# taGPS-1350.net
KiCad netlist of a schematic drawn in EAGLE
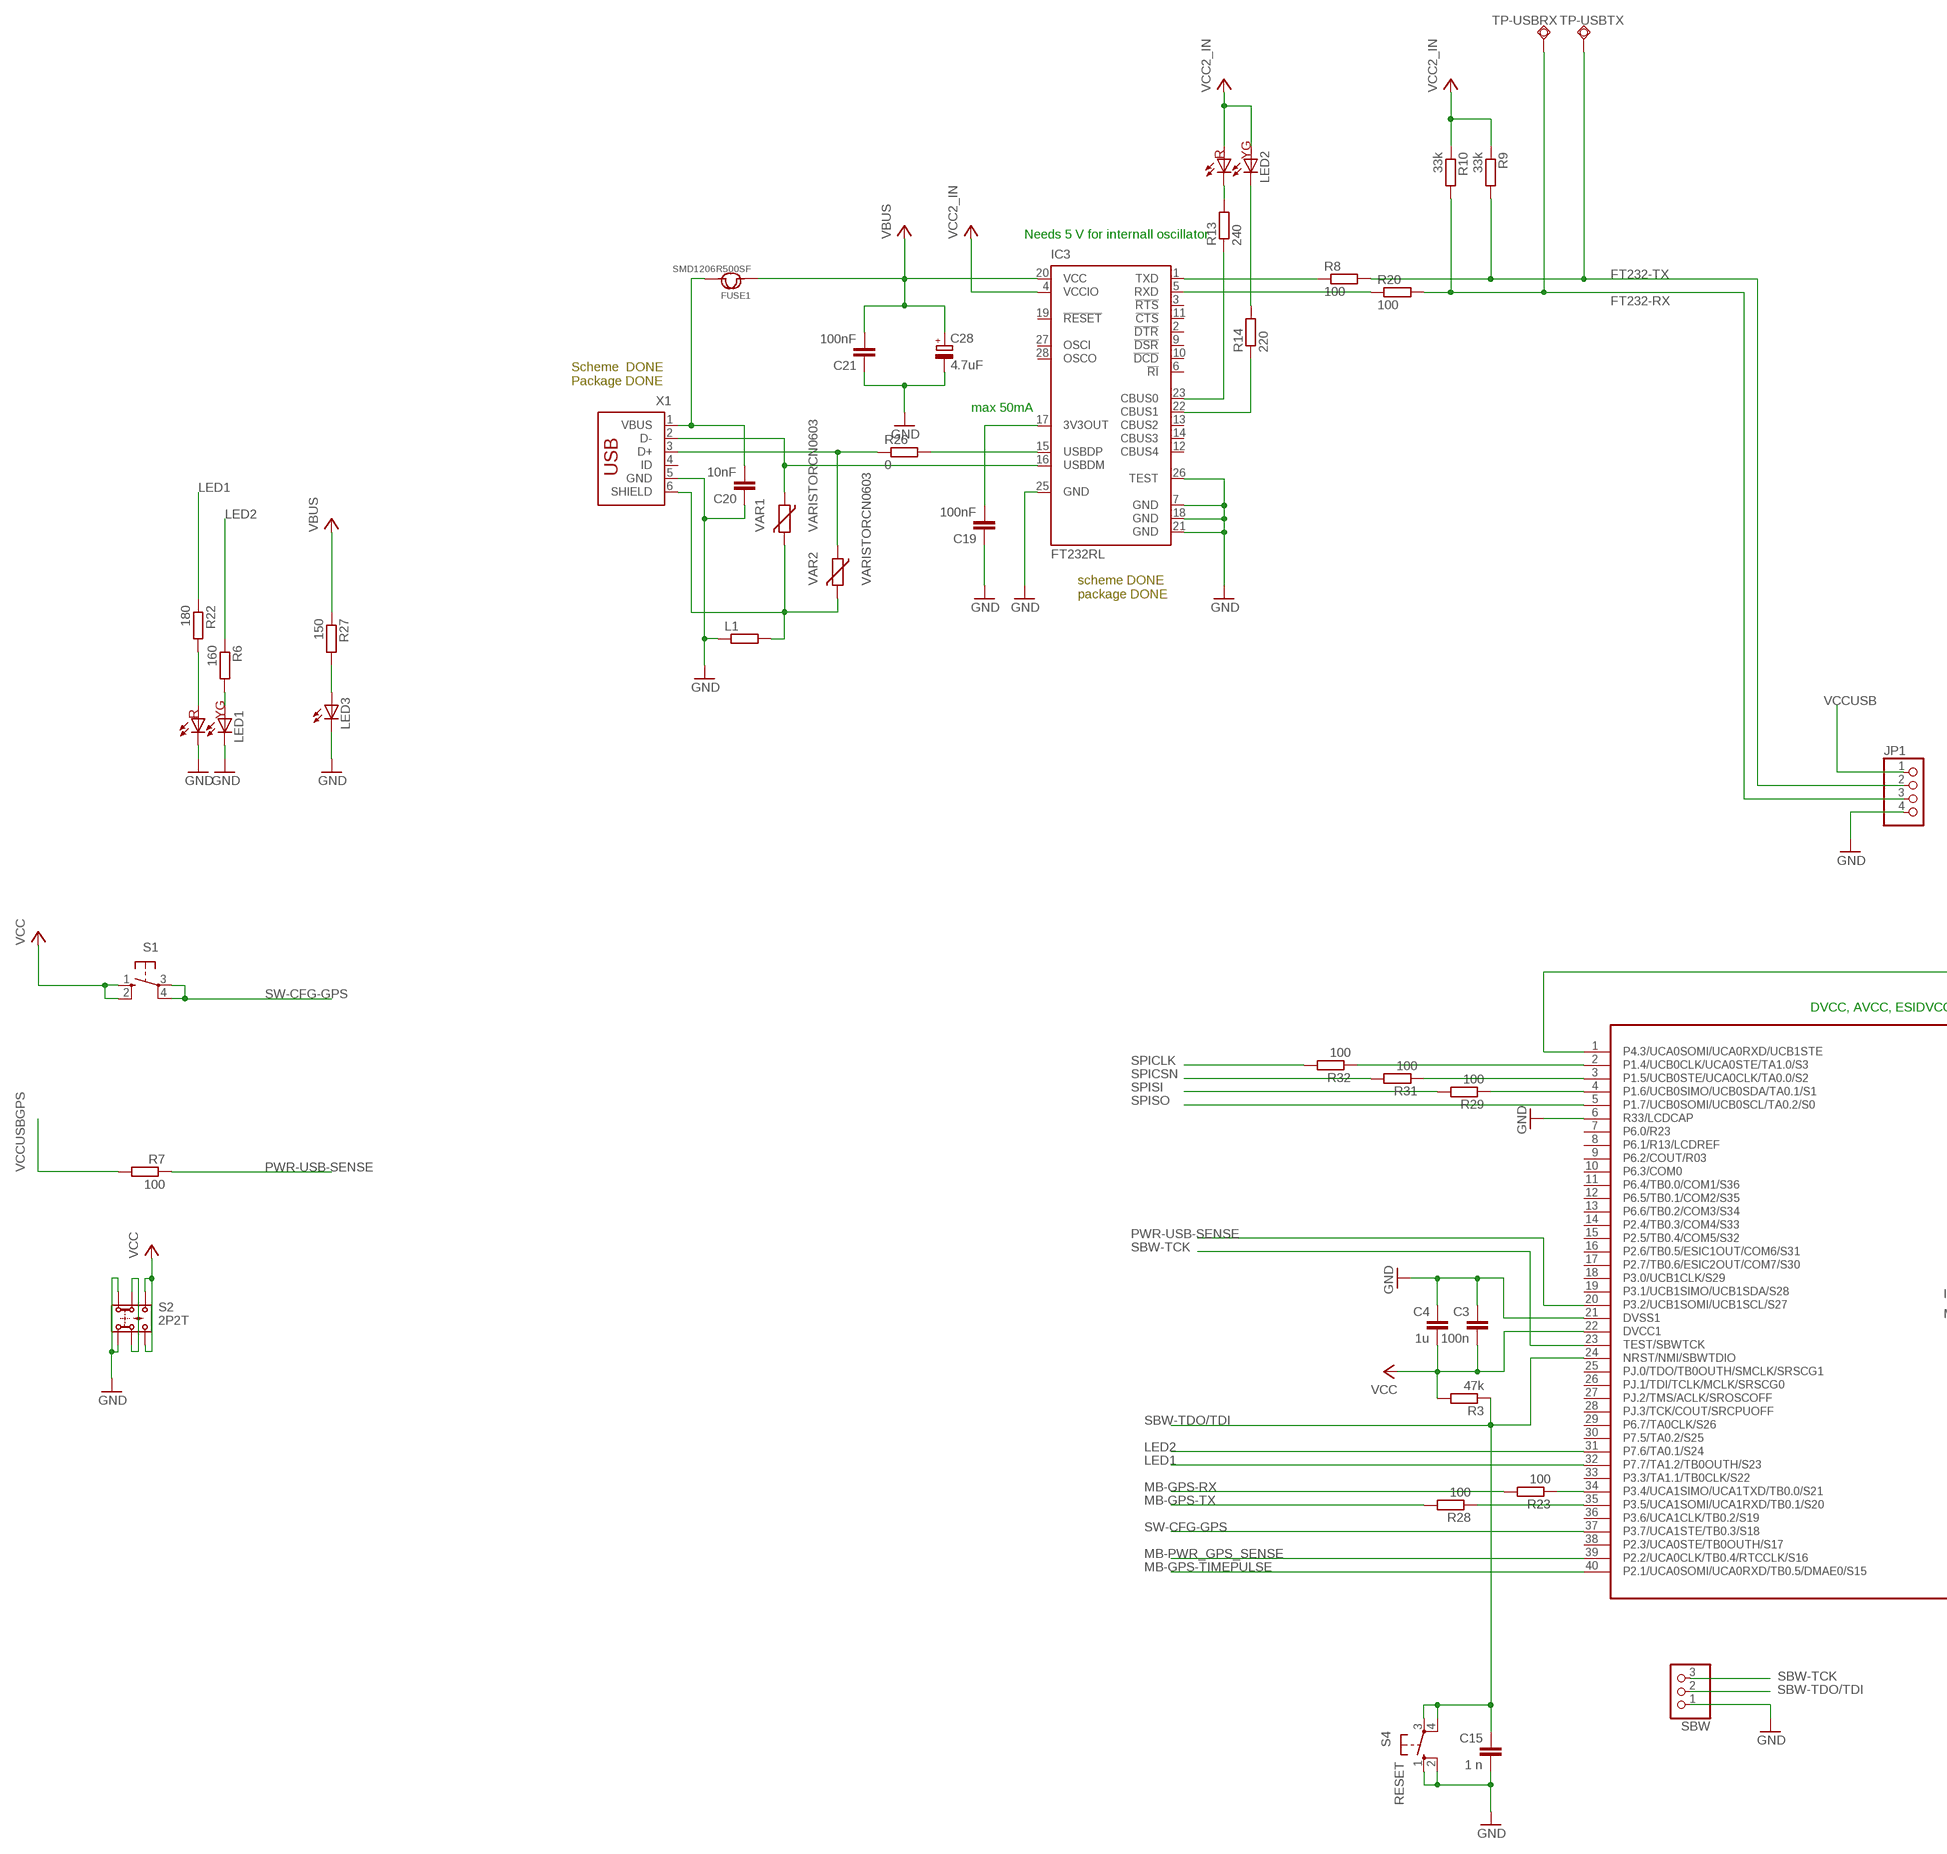
[diagram p0: schematic, sheet 1, part 1 of 2]
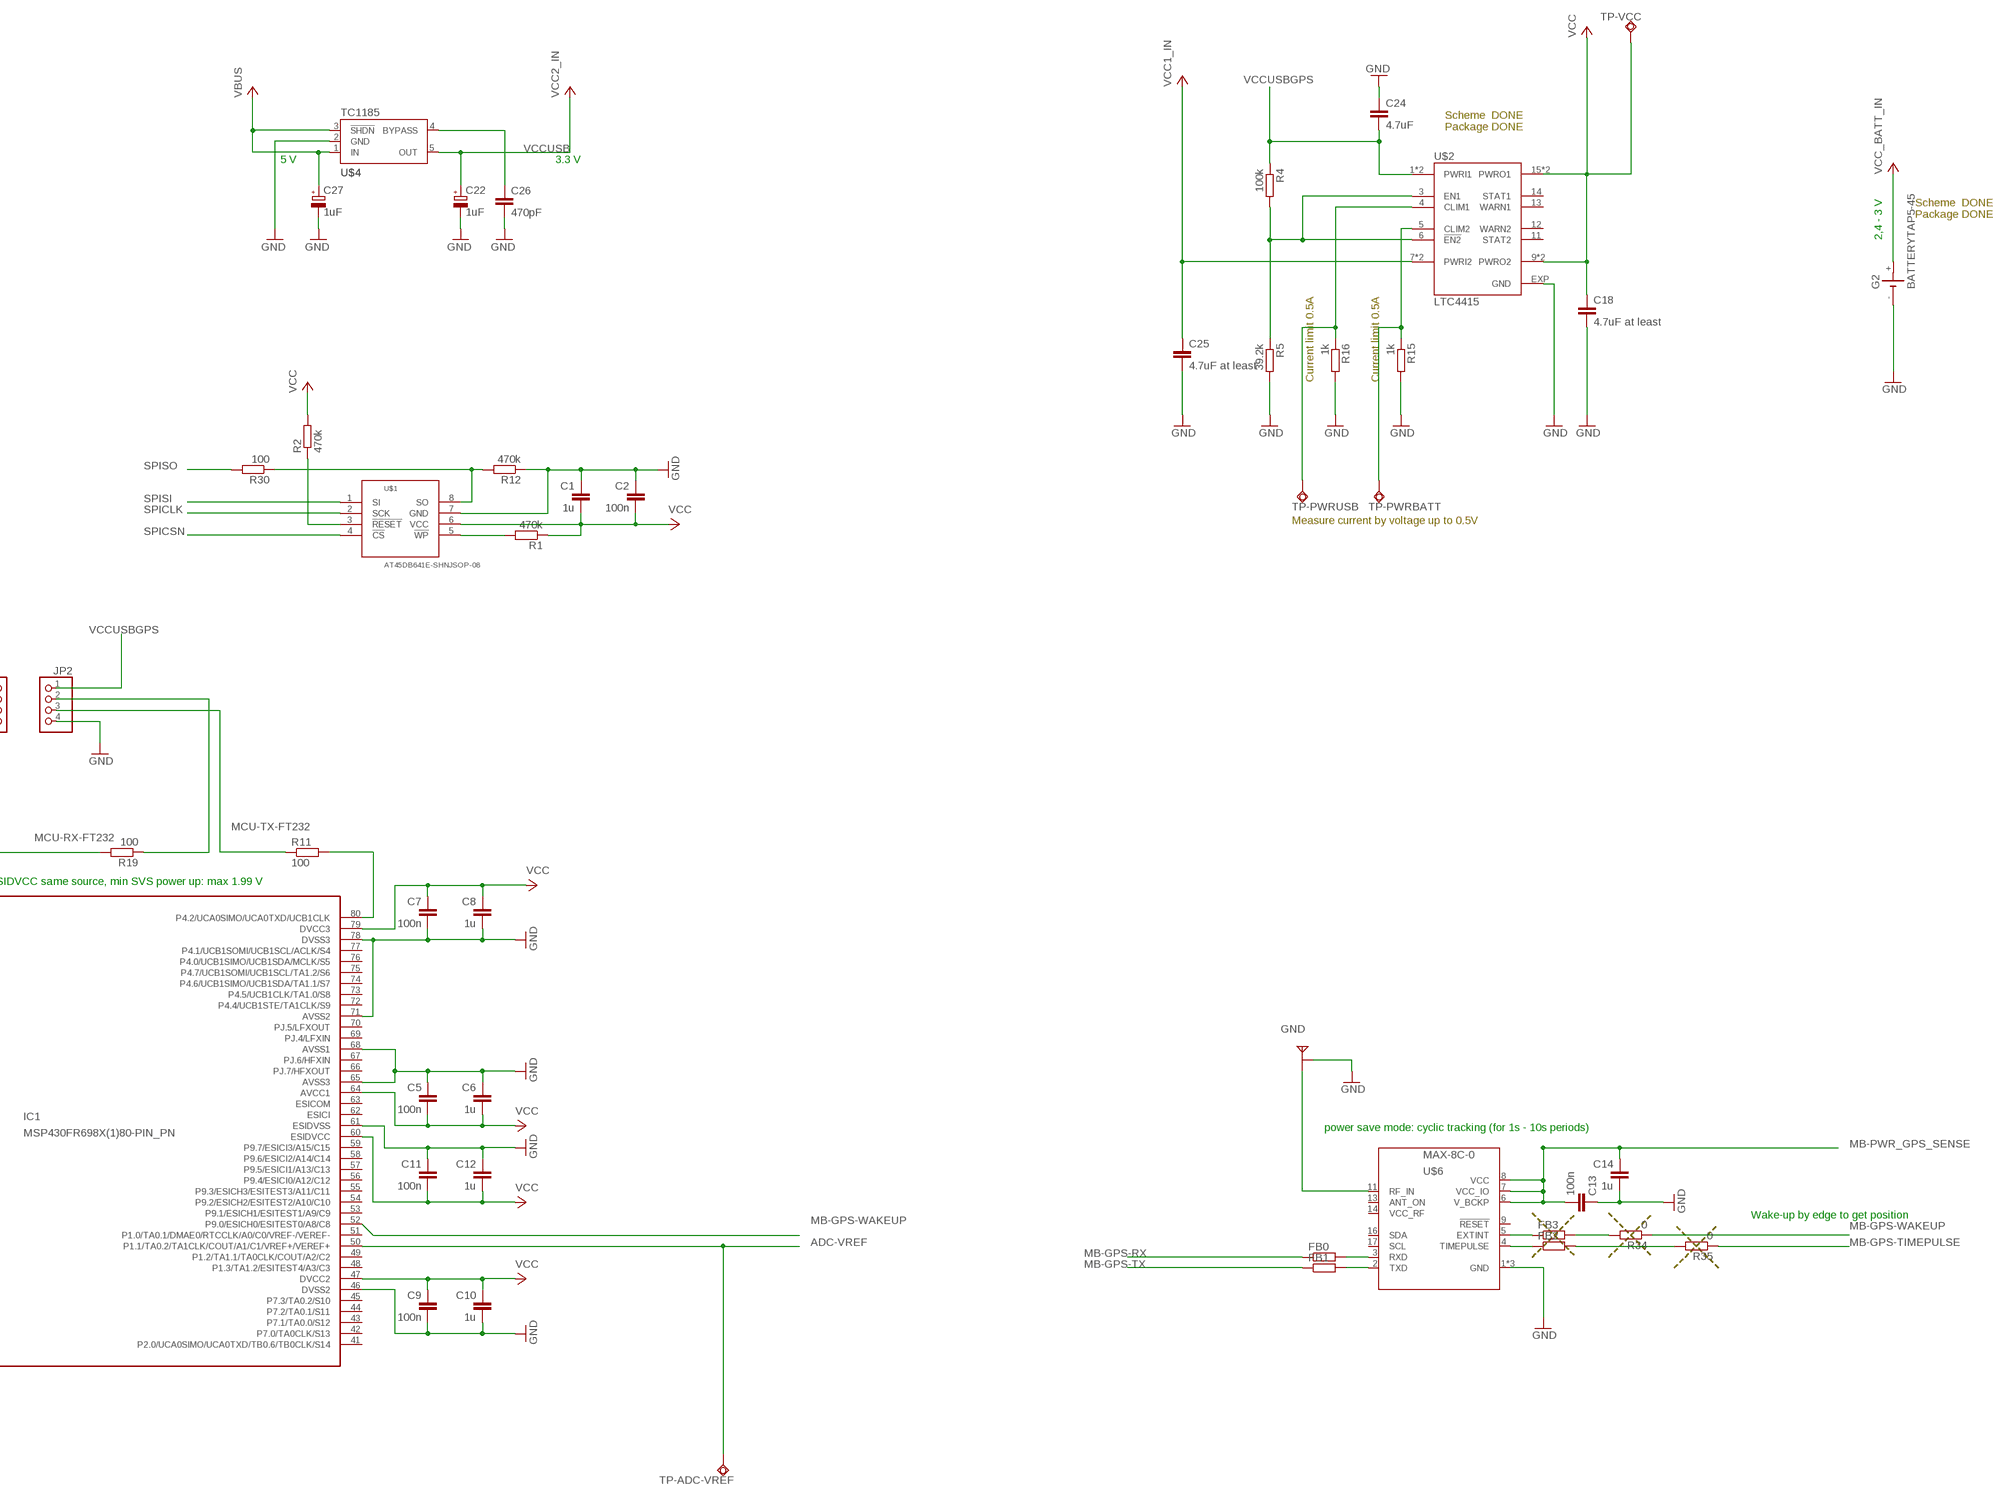
[diagram p1: schematic, sheet 1, part 2 of 2]

(export (version "E")
  (design (tool "Eeschema 10.0.6"))
  (components
    (comp (ref "C1")
      (value "1u")
      (footprint "eagle-import:C0603")
      (libsource (lib "eagle-import") (part "C-EUC0603"))
    )
    (comp (ref "C2")
      (value "100n")
      (footprint "eagle-import:C0603")
      (libsource (lib "eagle-import") (part "C-EUC0603"))
    )
    (comp (ref "C3")
      (value "100n")
      (footprint "eagle-import:C0603")
      (libsource (lib "eagle-import") (part "C-EUC0603"))
    )
    (comp (ref "C4")
      (value "1u")
      (footprint "eagle-import:C0603")
      (libsource (lib "eagle-import") (part "C-EUC0603"))
    )
    (comp (ref "C5")
      (value "100n")
      (footprint "eagle-import:C0603")
      (libsource (lib "eagle-import") (part "C-EUC0603"))
    )
    (comp (ref "C6")
      (value "1u")
      (footprint "eagle-import:C0603")
      (libsource (lib "eagle-import") (part "C-EUC0603"))
    )
    (comp (ref "C7")
      (value "100n")
      (footprint "eagle-import:C0603")
      (libsource (lib "eagle-import") (part "C-EUC0603"))
    )
    (comp (ref "C8")
      (value "1u")
      (footprint "eagle-import:C0603")
      (libsource (lib "eagle-import") (part "C-EUC0603"))
    )
    (comp (ref "C9")
      (value "100n")
      (footprint "eagle-import:C0603")
      (libsource (lib "eagle-import") (part "C-EUC0603"))
    )
    (comp (ref "C10")
      (value "1u")
      (footprint "eagle-import:C0603")
      (libsource (lib "eagle-import") (part "C-EUC0603"))
    )
    (comp (ref "C11")
      (value "100n")
      (footprint "eagle-import:C0603")
      (libsource (lib "eagle-import") (part "C-EUC0603"))
    )
    (comp (ref "C12")
      (value "1u")
      (footprint "eagle-import:C0603")
      (libsource (lib "eagle-import") (part "C-EUC0603"))
    )
    (comp (ref "C13")
      (value "100n")
      (footprint "eagle-import:C0603")
      (libsource (lib "eagle-import") (part "C-EUC0603"))
    )
    (comp (ref "C14")
      (value "1u")
      (footprint "eagle-import:C0603")
      (libsource (lib "eagle-import") (part "C-EUC0603"))
    )
    (comp (ref "C15")
      (value "1 n")
      (footprint "eagle-import:C0603")
      (libsource (lib "eagle-import") (part "C-EUC0603"))
    )
    (comp (ref "C18")
      (value "4.7uF at least")
      (footprint "eagle-import:C0805")
      (libsource (lib "eagle-import") (part "C-EUC0805"))
    )
    (comp (ref "C19")
      (value "100nF")
      (footprint "eagle-import:C0603")
      (libsource (lib "eagle-import") (part "C-EUC0603"))
    )
    (comp (ref "C20")
      (value "10nF")
      (footprint "eagle-import:C0603")
      (libsource (lib "eagle-import") (part "C-EUC0603"))
    )
    (comp (ref "C21")
      (value "100nF")
      (footprint "eagle-import:C0603")
      (libsource (lib "eagle-import") (part "C-EUC0603"))
    )
    (comp (ref "C22")
      (value "1uF")
      (footprint "eagle-import:A_3216-18W")
      (libsource (lib "eagle-import") (part "CPOL-EUA/3216-18W"))
    )
    (comp (ref "C24")
      (value "4.7uF")
      (footprint "eagle-import:C0805")
      (libsource (lib "eagle-import") (part "C-EUC0805"))
    )
    (comp (ref "C25")
      (value "4.7uF at least")
      (footprint "eagle-import:C0805")
      (libsource (lib "eagle-import") (part "C-EUC0805"))
    )
    (comp (ref "C26")
      (value "470pF")
      (footprint "eagle-import:C0603")
      (libsource (lib "eagle-import") (part "C-EUC0603"))
    )
    (comp (ref "C27")
      (value "1uF")
      (footprint "eagle-import:A_3216-18W")
      (libsource (lib "eagle-import") (part "CPOL-EUA/3216-18W"))
    )
    (comp (ref "C28")
      (value "4.7uF")
      (footprint "eagle-import:A_3216-18W")
      (libsource (lib "eagle-import") (part "CPOL-EUA/3216-18W"))
    )
    (comp (ref "FB0")
      (value "R-EU_R0402")
      (footprint "eagle-import:R0402")
      (libsource (lib "eagle-import") (part "R-EU_R0402"))
    )
    (comp (ref "FB1")
      (value "R-EU_R0402")
      (footprint "eagle-import:R0402")
      (libsource (lib "eagle-import") (part "R-EU_R0402"))
    )
    (comp (ref "FB2")
      (value "R-EU_R0402")
      (footprint "eagle-import:R0402")
      (libsource (lib "eagle-import") (part "R-EU_R0402"))
    )
    (comp (ref "FB3")
      (value "R-EU_R0402")
      (footprint "eagle-import:R0402")
      (libsource (lib "eagle-import") (part "R-EU_R0402"))
    )
    (comp (ref "FUSE1")
      (value "SMD1206R500SF")
      (footprint "eagle-import:F1812")
      (libsource (lib "eagle-import") (part "SMD-PPTC-500MA-15V(1812)"))
    )
    (comp (ref "G2")
      (value "BATTERYTAP5-45")
      (footprint "eagle-import:TAP5-45")
      (libsource (lib "eagle-import") (part "BATTERYTAP5-45"))
    )
    (comp (ref "IC1")
      (value "MSP430FR698X(1)80-PIN_PN")
      (footprint "eagle-import:PN_S-PQFP-G80")
      (libsource (lib "eagle-import") (part "MSP430FR698X(1)80-PIN_PN"))
    )
    (comp (ref "IC3")
      (value "FT232RL")
      (footprint "eagle-import:SSOP28")
      (libsource (lib "eagle-import") (part "FT232RL"))
    )
    (comp (ref "JP1")
      (value "PINHD-1X4")
      (footprint "eagle-import:1X04")
      (libsource (lib "eagle-import") (part "PINHD-1X4"))
    )
    (comp (ref "JP2")
      (value "PINHD-1X4")
      (footprint "eagle-import:1X04")
      (libsource (lib "eagle-import") (part "PINHD-1X4"))
    )
    (comp (ref "L1")
      (value "R-EU_R0603")
      (footprint "eagle-import:R0603")
      (libsource (lib "eagle-import") (part "R-EU_R0603"))
    )
    (comp (ref "LED1")
      (value "BILEDBILED")
      (footprint "eagle-import:BILED")
      (libsource (lib "eagle-import") (part "BILEDBILED"))
    )
    (comp (ref "LED2")
      (value "BILEDBILED")
      (footprint "eagle-import:BILED")
      (libsource (lib "eagle-import") (part "BILEDBILED"))
    )
    (comp (ref "LED3")
      (value "LED_E")
      (footprint "eagle-import:LED_KINGBRIGHT0603")
      (libsource (lib "eagle-import") (part "LED_E"))
    )
    (comp (ref "R1")
      (value "470k")
      (footprint "eagle-import:R0603")
      (libsource (lib "eagle-import") (part "R-EU_R0603"))
    )
    (comp (ref "R2")
      (value "470k")
      (footprint "eagle-import:R0603")
      (libsource (lib "eagle-import") (part "R-EU_R0603"))
    )
    (comp (ref "R3")
      (value "47k")
      (footprint "eagle-import:R0603")
      (libsource (lib "eagle-import") (part "R-EU_R0603"))
    )
    (comp (ref "R4")
      (value "100k")
      (footprint "eagle-import:R0603")
      (libsource (lib "eagle-import") (part "R-EU_R0603"))
    )
    (comp (ref "R5")
      (value "39.2k")
      (footprint "eagle-import:R0603")
      (libsource (lib "eagle-import") (part "R-EU_R0603"))
    )
    (comp (ref "R6")
      (value "160")
      (footprint "eagle-import:R0603")
      (libsource (lib "eagle-import") (part "R-EU_R0603"))
    )
    (comp (ref "R7")
      (value "100")
      (footprint "eagle-import:R0603")
      (libsource (lib "eagle-import") (part "R-EU_R0603"))
    )
    (comp (ref "R8")
      (value "100")
      (footprint "eagle-import:R0603")
      (libsource (lib "eagle-import") (part "R-EU_R0603"))
    )
    (comp (ref "R9")
      (value "33k")
      (footprint "eagle-import:R0603")
      (libsource (lib "eagle-import") (part "R-EU_R0603"))
    )
    (comp (ref "R10")
      (value "33k")
      (footprint "eagle-import:R0603")
      (libsource (lib "eagle-import") (part "R-EU_R0603"))
    )
    (comp (ref "R11")
      (value "100")
      (footprint "eagle-import:R0603")
      (libsource (lib "eagle-import") (part "R-EU_R0603"))
    )
    (comp (ref "R12")
      (value "470k")
      (footprint "eagle-import:R0603")
      (libsource (lib "eagle-import") (part "R-EU_R0603"))
    )
    (comp (ref "R13")
      (value "240")
      (footprint "eagle-import:R0603")
      (libsource (lib "eagle-import") (part "R-EU_R0603"))
    )
    (comp (ref "R14")
      (value "220")
      (footprint "eagle-import:R0603")
      (libsource (lib "eagle-import") (part "R-EU_R0603"))
    )
    (comp (ref "R15")
      (value "1k")
      (footprint "eagle-import:R0603")
      (libsource (lib "eagle-import") (part "R-EU_R0603"))
    )
    (comp (ref "R16")
      (value "1k")
      (footprint "eagle-import:R0603")
      (libsource (lib "eagle-import") (part "R-EU_R0603"))
    )
    (comp (ref "R19")
      (value "100")
      (footprint "eagle-import:R0603")
      (libsource (lib "eagle-import") (part "R-EU_R0603"))
    )
    (comp (ref "R20")
      (value "100")
      (footprint "eagle-import:R0603")
      (libsource (lib "eagle-import") (part "R-EU_R0603"))
    )
    (comp (ref "R22")
      (value "180")
      (footprint "eagle-import:R0603")
      (libsource (lib "eagle-import") (part "R-EU_R0603"))
    )
    (comp (ref "R23")
      (value "100")
      (footprint "eagle-import:R0603")
      (libsource (lib "eagle-import") (part "R-EU_R0603"))
    )
    (comp (ref "R26")
      (value "0")
      (footprint "eagle-import:R0603")
      (libsource (lib "eagle-import") (part "R-EU_R0603"))
    )
    (comp (ref "R27")
      (value "150")
      (footprint "eagle-import:R0603")
      (libsource (lib "eagle-import") (part "R-EU_R0603"))
    )
    (comp (ref "R28")
      (value "100")
      (footprint "eagle-import:R0603")
      (libsource (lib "eagle-import") (part "R-EU_R0603"))
    )
    (comp (ref "R29")
      (value "100")
      (footprint "eagle-import:R0603")
      (libsource (lib "eagle-import") (part "R-EU_R0603"))
    )
    (comp (ref "R30")
      (value "100")
      (footprint "eagle-import:R0603")
      (libsource (lib "eagle-import") (part "R-EU_R0603"))
    )
    (comp (ref "R31")
      (value "100")
      (footprint "eagle-import:R0603")
      (libsource (lib "eagle-import") (part "R-EU_R0603"))
    )
    (comp (ref "R32")
      (value "100")
      (footprint "eagle-import:R0603")
      (libsource (lib "eagle-import") (part "R-EU_R0603"))
    )
    (comp (ref "R34")
      (value "0")
      (footprint "eagle-import:R0603")
      (libsource (lib "eagle-import") (part "R-EU_R0603"))
    )
    (comp (ref "R35")
      (value "0")
      (footprint "eagle-import:R0603")
      (libsource (lib "eagle-import") (part "R-EU_R0603"))
    )
    (comp (ref "S1")
      (value "SWITCH-10-XX")
      (footprint "eagle-import:B3F-10XX")
      (fields (field (name "MPN") "B3F-1000"))
      (libsource (lib "eagle-import") (part "SWITCH-10-XX"))
    )
    (comp (ref "S2")
      (value "2P2T")
      (footprint "eagle-import:2P2T")
      (libsource (lib "eagle-import") (part "2P2T"))
    )
    (comp (ref "S4")
      (value "RESET")
      (footprint "eagle-import:B3F-10XX")
      (fields (field (name "MPN") "B3F-1000"))
      (libsource (lib "eagle-import") (part "SWITCH-10-XX"))
    )
    (comp (ref "SBW")
      (value "PINHD-1X3")
      (footprint "eagle-import:1X03")
      (libsource (lib "eagle-import") (part "PINHD-1X3"))
    )
    (comp (ref "TP-ADC-VREF")
      (value "TPSQTP10R")
      (footprint "eagle-import:TP10R")
      (libsource (lib "eagle-import") (part "TPSQTP10R"))
    )
    (comp (ref "TP-PWRBATT")
      (value "TPSQTP10R")
      (footprint "eagle-import:TP10R")
      (libsource (lib "eagle-import") (part "TPSQTP10R"))
    )
    (comp (ref "TP-PWRUSB")
      (value "TPSQTP10R")
      (footprint "eagle-import:TP10R")
      (libsource (lib "eagle-import") (part "TPSQTP10R"))
    )
    (comp (ref "TP-USBRX")
      (value "TPSQPAD1-13")
      (footprint "eagle-import:P1-13")
      (libsource (lib "eagle-import") (part "TPSQPAD1-13"))
    )
    (comp (ref "TP-USBTX")
      (value "TPSQPAD1-13")
      (footprint "eagle-import:P1-13")
      (libsource (lib "eagle-import") (part "TPSQPAD1-13"))
    )
    (comp (ref "TP-VCC")
      (value "TPSQTP10R")
      (footprint "eagle-import:TP10R")
      (libsource (lib "eagle-import") (part "TPSQTP10R"))
    )
    (comp (ref "U$1")
      (value "AT45DB641E-SHNJSOP-08")
      (footprint "eagle-import:JSOP-08")
      (libsource (lib "eagle-import") (part "AT45DB641E-SHNJSOP-08"))
    )
    (comp (ref "U$2")
      (value "LTC4415")
      (footprint "eagle-import:MSOP16")
      (libsource (lib "eagle-import") (part "LTC4415"))
    )
    (comp (ref "U$4")
      (value "TC1185")
      (footprint "eagle-import:SOT23-5")
      (libsource (lib "eagle-import") (part "TC1185"))
    )
    (comp (ref "U$5")
      (value "MWSL1251MWSL1350")
      (footprint "eagle-import:MWSL1350")
      (libsource (lib "eagle-import") (part "MWSL1251MWSL1350"))
    )
    (comp (ref "U$6")
      (value "MAX-8C-0")
      (footprint "eagle-import:MAX-8")
      (libsource (lib "eagle-import") (part "MAX-8C-0"))
    )
    (comp (ref "VAR1")
      (value "VARISTORCN0603")
      (footprint "eagle-import:CT_CN0603")
      (libsource (lib "eagle-import") (part "VARISTORCN0603"))
    )
    (comp (ref "VAR2")
      (value "VARISTORCN0603")
      (footprint "eagle-import:CT_CN0603")
      (libsource (lib "eagle-import") (part "VARISTORCN0603"))
    )
    (comp (ref "X1")
      (value "USB-787616")
      (footprint "eagle-import:USB")
      (libsource (lib "eagle-import") (part "USB-787616"))
    )
  )
  (nets
    (net (code "1") (name "/ADC-VREF") (class "Default")
      (node (ref "IC1") (pin "50") (pinfunction "P1.1/TA0.2/TA1CLK/COUT/A1/C1/VREF+/VEREF+_50") (pintype "bidirectional"))
      (node (ref "TP-ADC-VREF") (pin "TP") (pinfunction "TP_TP") (pintype "input"))
    )
    (net (code "2") (name "/FT232-RX") (class "Default")
      (node (ref "JP1") (pin "3") (pinfunction "3_3") (pintype "passive"))
      (node (ref "R10") (pin "2") (pinfunction "2_2") (pintype "passive"))
      (node (ref "R20") (pin "2") (pinfunction "2_2") (pintype "passive"))
      (node (ref "TP-USBRX") (pin "TP") (pinfunction "TP_TP") (pintype "input"))
    )
    (net (code "3") (name "/FT232-TX") (class "Default")
      (node (ref "JP1") (pin "2") (pinfunction "2_2") (pintype "passive"))
      (node (ref "R8") (pin "2") (pinfunction "2_2") (pintype "passive"))
      (node (ref "R9") (pin "2") (pinfunction "2_2") (pintype "passive"))
      (node (ref "TP-USBTX") (pin "TP") (pinfunction "TP_TP") (pintype "input"))
    )
    (net (code "4") (name "/LED1") (class "Default")
      (node (ref "IC1") (pin "32") (pinfunction "P7.7/TA1.2/TB0OUTH/S23_32") (pintype "bidirectional"))
      (node (ref "R22") (pin "1") (pinfunction "1_1") (pintype "passive"))
    )
    (net (code "5") (name "/LED2") (class "Default")
      (node (ref "IC1") (pin "31") (pinfunction "P7.6/TA0.1/S24_31") (pintype "bidirectional"))
      (node (ref "R6") (pin "1") (pinfunction "1_1") (pintype "passive"))
    )
    (net (code "6") (name "/MB-GPS-RX") (class "Default")
      (node (ref "FB0") (pin "1") (pinfunction "1_1") (pintype "passive"))
      (node (ref "R23") (pin "2") (pinfunction "2_2") (pintype "passive"))
    )
    (net (code "7") (name "/MB-GPS-TIMEPULSE") (class "Default")
      (node (ref "IC1") (pin "40") (pinfunction "P2.1/UCA0SOMI/UCA0RXD/TB0.5/DMAE0/S15_40") (pintype "bidirectional"))
      (node (ref "R35") (pin "1") (pinfunction "1_1") (pintype "passive"))
    )
    (net (code "8") (name "/MB-GPS-TX") (class "Default")
      (node (ref "FB1") (pin "1") (pinfunction "1_1") (pintype "passive"))
      (node (ref "R28") (pin "2") (pinfunction "2_2") (pintype "passive"))
    )
    (net (code "9") (name "/MB-GPS-WAKEUP") (class "Default")
      (node (ref "IC1") (pin "52") (pinfunction "P9.0/ESICH0/ESITEST0/A8/C8_52") (pintype "bidirectional"))
      (node (ref "R34") (pin "1") (pinfunction "1_1") (pintype "passive"))
    )
    (net (code "10") (name "/MB-PWR_GPS_SENSE") (class "Default")
      (node (ref "C13") (pin "2") (pinfunction "2_2") (pintype "passive"))
      (node (ref "C14") (pin "1") (pinfunction "1_1") (pintype "passive"))
      (node (ref "IC1") (pin "39") (pinfunction "P2.2/UCA0CLK/TB0.4/RTCCLK/S16_39") (pintype "bidirectional"))
      (node (ref "S2") (pin "2.1") (pinfunction "2.1_2.1") (pintype "passive"))
      (node (ref "S2") (pin "2.2") (pinfunction "2.2_2.2") (pintype "passive"))
      (node (ref "U$6") (pin "6") (pinfunction "V_BCKP_6") (pintype "power_in"))
      (node (ref "U$6") (pin "7") (pinfunction "VCC_IO_7") (pintype "power_in"))
      (node (ref "U$6") (pin "8") (pinfunction "VCC_8") (pintype "power_in"))
    )
    (net (code "11") (name "/MCU-RX-FT232") (class "Default")
      (node (ref "IC1") (pin "1") (pinfunction "P4.3/UCA0SOMI/UCA0RXD/UCB1STE_1") (pintype "bidirectional"))
      (node (ref "R19") (pin "2") (pinfunction "2_2") (pintype "passive"))
    )
    (net (code "12") (name "/MCU-TX-FT232") (class "Default")
      (node (ref "JP2") (pin "3") (pinfunction "3_3") (pintype "passive"))
      (node (ref "R11") (pin "1") (pinfunction "1_1") (pintype "passive"))
    )
    (net (code "13") (name "/PWR-USB-SENSE") (class "Default")
      (node (ref "IC1") (pin "20") (pinfunction "P3.2/UCB1SOMI/UCB1SCL/S27_20") (pintype "bidirectional"))
      (node (ref "R7") (pin "1") (pinfunction "1_1") (pintype "passive"))
    )
    (net (code "14") (name "/SBW-TCK") (class "Default")
      (node (ref "IC1") (pin "23") (pinfunction "TEST/SBWTCK_23") (pintype "output"))
      (node (ref "SBW") (pin "3") (pinfunction "3_3") (pintype "passive"))
    )
    (net (code "15") (name "/SBW-TDO{slash}TDI") (class "Default")
      (node (ref "C15") (pin "1") (pinfunction "1_1") (pintype "passive"))
      (node (ref "IC1") (pin "24") (pinfunction "NRST/NMI/SBWTDIO_24") (pintype "bidirectional"))
      (node (ref "R3") (pin "1") (pinfunction "1_1") (pintype "passive"))
      (node (ref "S4") (pin "3") (pinfunction "P_3") (pintype "passive"))
      (node (ref "S4") (pin "4") (pinfunction "P1_4") (pintype "passive"))
      (node (ref "SBW") (pin "2") (pinfunction "2_2") (pintype "passive"))
    )
    (net (code "16") (name "/SPICLK") (class "Default")
      (node (ref "R32") (pin "2") (pinfunction "2_2") (pintype "passive"))
      (node (ref "U$1") (pin "2") (pinfunction "SCK_2") (pintype "input"))
    )
    (net (code "17") (name "/SPICSN") (class "Default")
      (node (ref "R31") (pin "2") (pinfunction "2_2") (pintype "passive"))
      (node (ref "U$1") (pin "4") (pinfunction "~{CS}_4") (pintype "input"))
    )
    (net (code "18") (name "/SPISI") (class "Default")
      (node (ref "R29") (pin "2") (pinfunction "2_2") (pintype "passive"))
      (node (ref "U$1") (pin "1") (pinfunction "SI_1") (pintype "input"))
    )
    (net (code "19") (name "/SPISO") (class "Default")
      (node (ref "IC1") (pin "5") (pinfunction "P1.7/UCB0SOMI/UCB0SCL/TA0.2/S0_5") (pintype "bidirectional"))
      (node (ref "R30") (pin "2") (pinfunction "2_2") (pintype "passive"))
    )
    (net (code "20") (name "/SW-CFG-GPS") (class "Default")
      (node (ref "IC1") (pin "37") (pinfunction "P3.7/UCA1STE/TB0.3/S18_37") (pintype "bidirectional"))
      (node (ref "S1") (pin "3") (pinfunction "P_3") (pintype "passive"))
      (node (ref "S1") (pin "4") (pinfunction "P1_4") (pintype "passive"))
    )
    (net (code "21") (name "/VCCUSBGPS") (class "Default")
      (node (ref "C24") (pin "2") (pinfunction "2_2") (pintype "passive"))
      (node (ref "JP2") (pin "1") (pinfunction "1_1") (pintype "passive"))
      (node (ref "R4") (pin "1") (pinfunction "1_1") (pintype "passive"))
      (node (ref "R7") (pin "2") (pinfunction "2_2") (pintype "passive"))
      (node (ref "U$2") (pin "1") (pinfunction "PWRI1_1") (pintype "power_in"))
      (node (ref "U$2") (pin "2") (pinfunction "PWRI1_2") (pintype "power_in"))
    )
    (net (code "22") (name "GND") (class "Default")
      (node (ref "C1") (pin "1") (pinfunction "1_1") (pintype "passive"))
      (node (ref "C10") (pin "2") (pinfunction "2_2") (pintype "passive"))
      (node (ref "C11") (pin "1") (pinfunction "1_1") (pintype "passive"))
      (node (ref "C12") (pin "1") (pinfunction "1_1") (pintype "passive"))
      (node (ref "C13") (pin "1") (pinfunction "1_1") (pintype "passive"))
      (node (ref "C14") (pin "2") (pinfunction "2_2") (pintype "passive"))
      (node (ref "C15") (pin "2") (pinfunction "2_2") (pintype "passive"))
      (node (ref "C18") (pin "2") (pinfunction "2_2") (pintype "passive"))
      (node (ref "C19") (pin "1") (pinfunction "1_1") (pintype "passive"))
      (node (ref "C2") (pin "1") (pinfunction "1_1") (pintype "passive"))
      (node (ref "C20") (pin "1") (pinfunction "1_1") (pintype "passive"))
      (node (ref "C21") (pin "1") (pinfunction "1_1") (pintype "passive"))
      (node (ref "C22") (pin "-") (pinfunction "-_-") (pintype "passive"))
      (node (ref "C24") (pin "1") (pinfunction "1_1") (pintype "passive"))
      (node (ref "C25") (pin "2") (pinfunction "2_2") (pintype "passive"))
      (node (ref "C26") (pin "2") (pinfunction "2_2") (pintype "passive"))
      (node (ref "C27") (pin "-") (pinfunction "-_-") (pintype "passive"))
      (node (ref "C28") (pin "-") (pinfunction "-_-") (pintype "passive"))
      (node (ref "C3") (pin "1") (pinfunction "1_1") (pintype "passive"))
      (node (ref "C4") (pin "1") (pinfunction "1_1") (pintype "passive"))
      (node (ref "C5") (pin "1") (pinfunction "1_1") (pintype "passive"))
      (node (ref "C6") (pin "1") (pinfunction "1_1") (pintype "passive"))
      (node (ref "C7") (pin "2") (pinfunction "2_2") (pintype "passive"))
      (node (ref "C8") (pin "2") (pinfunction "2_2") (pintype "passive"))
      (node (ref "C9") (pin "2") (pinfunction "2_2") (pintype "passive"))
      (node (ref "G2") (pin "-") (pinfunction "-_-") (pintype "passive"))
      (node (ref "IC1") (pin "21") (pinfunction "DVSS1_21") (pintype "power_in"))
      (node (ref "IC1") (pin "46") (pinfunction "DVSS2_46") (pintype "power_in"))
      (node (ref "IC1") (pin "6") (pinfunction "R33/LCDCAP_6") (pintype "bidirectional"))
      (node (ref "IC1") (pin "61") (pinfunction "ESIDVSS_61") (pintype "power_in"))
      (node (ref "IC1") (pin "65") (pinfunction "AVSS3_65") (pintype "power_in"))
      (node (ref "IC1") (pin "68") (pinfunction "AVSS1_68") (pintype "power_in"))
      (node (ref "IC1") (pin "71") (pinfunction "AVSS2_71") (pintype "power_in"))
      (node (ref "IC1") (pin "78") (pinfunction "DVSS3_78") (pintype "power_in"))
      (node (ref "IC3") (pin "18") (pinfunction "GND_18") (pintype "power_in"))
      (node (ref "IC3") (pin "21") (pinfunction "GND_21") (pintype "power_in"))
      (node (ref "IC3") (pin "25") (pinfunction "GND_25") (pintype "power_in"))
      (node (ref "IC3") (pin "26") (pinfunction "TEST_26") (pintype "input"))
      (node (ref "IC3") (pin "7") (pinfunction "GND_7") (pintype "power_in"))
      (node (ref "JP1") (pin "4") (pinfunction "4_4") (pintype "passive"))
      (node (ref "JP2") (pin "4") (pinfunction "4_4") (pintype "passive"))
      (node (ref "L1") (pin "1") (pinfunction "1_1") (pintype "passive"))
      (node (ref "LED1") (pin "1") (pinfunction "1_1") (pintype "passive"))
      (node (ref "LED1") (pin "3") (pinfunction "3_3") (pintype "passive"))
      (node (ref "LED3") (pin "C") (pinfunction "C_C") (pintype "passive"))
      (node (ref "R12") (pin "1") (pinfunction "1_1") (pintype "passive"))
      (node (ref "R15") (pin "2") (pinfunction "2_2") (pintype "passive"))
      (node (ref "R16") (pin "2") (pinfunction "2_2") (pintype "passive"))
      (node (ref "R5") (pin "2") (pinfunction "2_2") (pintype "passive"))
      (node (ref "S2") (pin "1.1") (pinfunction "1.1_1.1") (pintype "passive"))
      (node (ref "S2") (pin "1.2") (pinfunction "1.2_1.2") (pintype "passive"))
      (node (ref "S4") (pin "1") (pinfunction "S_1") (pintype "passive"))
      (node (ref "S4") (pin "2") (pinfunction "S1_2") (pintype "passive"))
      (node (ref "SBW") (pin "1") (pinfunction "1_1") (pintype "passive"))
      (node (ref "U$1") (pin "7") (pinfunction "GND_7") (pintype "power_in"))
      (node (ref "U$2") (pin "EXP") (pinfunction "GND_EXP") (pintype "power_in"))
      (node (ref "U$4") (pin "2") (pinfunction "GND_2") (pintype "power_in"))
      (node (ref "U$5") (pin "P$1") (pinfunction "GND_P$1") (pintype "power_in"))
      (node (ref "U$5") (pin "P$3") (pinfunction "GND_P$3") (pintype "power_in"))
      (node (ref "U$6") (pin "1") (pinfunction "GND_1") (pintype "power_in"))
      (node (ref "U$6") (pin "10") (pinfunction "GND_10") (pintype "power_in"))
      (node (ref "U$6") (pin "12") (pinfunction "GND_12") (pintype "power_in"))
      (node (ref "X1") (pin "5") (pinfunction "GND_5") (pintype "passive"))
    )
    (net (code "23") (name "Net-(FB2-Pad2)") (class "Default")
      (node (ref "FB2") (pin "2") (pinfunction "2_2") (pintype "passive"))
      (node (ref "R35") (pin "2") (pinfunction "2_2") (pintype "passive"))
    )
    (net (code "24") (name "Net-(FB3-Pad2)") (class "Default")
      (node (ref "FB3") (pin "2") (pinfunction "2_2") (pintype "passive"))
      (node (ref "R34") (pin "2") (pinfunction "2_2") (pintype "passive"))
    )
    (net (code "25") (name "Net-(IC1-P1.4{slash}UCB0CLK{slash}UCA0STE{slash}TA1.0{slash}S3)") (class "Default")
      (node (ref "IC1") (pin "2") (pinfunction "P1.4/UCB0CLK/UCA0STE/TA1.0/S3_2") (pintype "bidirectional"))
      (node (ref "R32") (pin "1") (pinfunction "1_1") (pintype "passive"))
    )
    (net (code "26") (name "Net-(IC1-P1.5{slash}UCB0STE{slash}UCA0CLK{slash}TA0.0{slash}S2)") (class "Default")
      (node (ref "IC1") (pin "3") (pinfunction "P1.5/UCB0STE/UCA0CLK/TA0.0/S2_3") (pintype "bidirectional"))
      (node (ref "R31") (pin "1") (pinfunction "1_1") (pintype "passive"))
    )
    (net (code "27") (name "Net-(IC1-P1.6{slash}UCB0SIMO{slash}UCB0SDA{slash}TA0.1{slash}S1)") (class "Default")
      (node (ref "IC1") (pin "4") (pinfunction "P1.6/UCB0SIMO/UCB0SDA/TA0.1/S1_4") (pintype "bidirectional"))
      (node (ref "R29") (pin "1") (pinfunction "1_1") (pintype "passive"))
    )
    (net (code "28") (name "Net-(IC1-P3.4{slash}UCA1SIMO{slash}UCA1TXD{slash}TB0.0{slash}S21)") (class "Default")
      (node (ref "IC1") (pin "34") (pinfunction "P3.4/UCA1SIMO/UCA1TXD/TB0.0/S21_34") (pintype "bidirectional"))
      (node (ref "R23") (pin "1") (pinfunction "1_1") (pintype "passive"))
    )
    (net (code "29") (name "Net-(IC1-P3.5{slash}UCA1SOMI{slash}UCA1RXD{slash}TB0.1{slash}S20)") (class "Default")
      (node (ref "IC1") (pin "35") (pinfunction "P3.5/UCA1SOMI/UCA1RXD/TB0.1/S20_35") (pintype "bidirectional"))
      (node (ref "R28") (pin "1") (pinfunction "1_1") (pintype "passive"))
    )
    (net (code "30") (name "Net-(IC1-P4.2{slash}UCA0SIMO{slash}UCA0TXD{slash}UCB1CLK)") (class "Default")
      (node (ref "IC1") (pin "80") (pinfunction "P4.2/UCA0SIMO/UCA0TXD/UCB1CLK_80") (pintype "bidirectional"))
      (node (ref "R11") (pin "2") (pinfunction "2_2") (pintype "passive"))
    )
    (net (code "31") (name "Net-(IC3-3V3OUT)") (class "Default")
      (node (ref "C19") (pin "2") (pinfunction "2_2") (pintype "passive"))
      (node (ref "IC3") (pin "17") (pinfunction "3V3OUT_17") (pintype "output"))
    )
    (net (code "32") (name "Net-(IC3-CBUS0)") (class "Default")
      (node (ref "IC3") (pin "23") (pinfunction "CBUS0_23") (pintype "bidirectional"))
      (node (ref "R13") (pin "1") (pinfunction "1_1") (pintype "passive"))
    )
    (net (code "33") (name "Net-(IC3-CBUS1)") (class "Default")
      (node (ref "IC3") (pin "22") (pinfunction "CBUS1_22") (pintype "bidirectional"))
      (node (ref "R14") (pin "1") (pinfunction "1_1") (pintype "passive"))
    )
    (net (code "34") (name "Net-(IC3-RXD)") (class "Default")
      (node (ref "IC3") (pin "5") (pinfunction "RXD_5") (pintype "input"))
      (node (ref "R20") (pin "1") (pinfunction "1_1") (pintype "passive"))
    )
    (net (code "35") (name "Net-(IC3-TXD)") (class "Default")
      (node (ref "IC3") (pin "1") (pinfunction "TXD_1") (pintype "output"))
      (node (ref "R8") (pin "1") (pinfunction "1_1") (pintype "passive"))
    )
    (net (code "36") (name "Net-(IC3-USBDM)") (class "Default")
      (node (ref "IC3") (pin "16") (pinfunction "USBDM_16") (pintype "bidirectional"))
      (node (ref "VAR1") (pin "1") (pinfunction "1_1") (pintype "passive"))
      (node (ref "X1") (pin "2") (pinfunction "D-_2") (pintype "passive"))
    )
    (net (code "37") (name "Net-(IC3-USBDP)") (class "Default")
      (node (ref "IC3") (pin "15") (pinfunction "USBDP_15") (pintype "bidirectional"))
      (node (ref "R26") (pin "2") (pinfunction "2_2") (pintype "passive"))
    )
    (net (code "38") (name "Net-(JP2-Pad2)") (class "Default")
      (node (ref "JP2") (pin "2") (pinfunction "2_2") (pintype "passive"))
      (node (ref "R19") (pin "1") (pinfunction "1_1") (pintype "passive"))
    )
    (net (code "39") (name "Net-(LED1-Pad2)") (class "Default")
      (node (ref "LED1") (pin "2") (pinfunction "2_2") (pintype "passive"))
      (node (ref "R22") (pin "2") (pinfunction "2_2") (pintype "passive"))
    )
    (net (code "40") (name "Net-(LED1-Pad4)") (class "Default")
      (node (ref "LED1") (pin "4") (pinfunction "4_4") (pintype "passive"))
      (node (ref "R6") (pin "2") (pinfunction "2_2") (pintype "passive"))
    )
    (net (code "41") (name "Net-(LED2-Pad1)") (class "Default")
      (node (ref "LED2") (pin "1") (pinfunction "1_1") (pintype "passive"))
      (node (ref "R13") (pin "2") (pinfunction "2_2") (pintype "passive"))
    )
    (net (code "42") (name "Net-(LED2-Pad3)") (class "Default")
      (node (ref "LED2") (pin "3") (pinfunction "3_3") (pintype "passive"))
      (node (ref "R14") (pin "2") (pinfunction "2_2") (pintype "passive"))
    )
    (net (code "43") (name "Net-(LED3-PadA)") (class "Default")
      (node (ref "LED3") (pin "A") (pinfunction "A_A") (pintype "passive"))
      (node (ref "R27") (pin "2") (pinfunction "2_2") (pintype "passive"))
    )
    (net (code "44") (name "Net-(U$1-SO)") (class "Default")
      (node (ref "R12") (pin "2") (pinfunction "2_2") (pintype "passive"))
      (node (ref "R30") (pin "1") (pinfunction "1_1") (pintype "passive"))
      (node (ref "U$1") (pin "8") (pinfunction "SO_8") (pintype "output"))
    )
    (net (code "45") (name "Net-(U$1-~{RESET})") (class "Default")
      (node (ref "R2") (pin "1") (pinfunction "1_1") (pintype "passive"))
      (node (ref "U$1") (pin "3") (pinfunction "~{RESET}_3") (pintype "input"))
    )
    (net (code "46") (name "Net-(U$1-~{WP})") (class "Default")
      (node (ref "R1") (pin "2") (pinfunction "2_2") (pintype "passive"))
      (node (ref "U$1") (pin "5") (pinfunction "~{WP}_5") (pintype "input"))
    )
    (net (code "47") (name "Net-(U$2-CLIM1)") (class "Default")
      (node (ref "R16") (pin "1") (pinfunction "1_1") (pintype "passive"))
      (node (ref "TP-PWRUSB") (pin "TP") (pinfunction "TP_TP") (pintype "input"))
      (node (ref "U$2") (pin "4") (pinfunction "CLIM1_4") (pintype "bidirectional"))
    )
    (net (code "48") (name "Net-(U$2-CLIM2)") (class "Default")
      (node (ref "R15") (pin "1") (pinfunction "1_1") (pintype "passive"))
      (node (ref "TP-PWRBATT") (pin "TP") (pinfunction "TP_TP") (pintype "input"))
      (node (ref "U$2") (pin "5") (pinfunction "CLIM2_5") (pintype "bidirectional"))
    )
    (net (code "49") (name "Net-(U$2-EN1)") (class "Default")
      (node (ref "R4") (pin "2") (pinfunction "2_2") (pintype "passive"))
      (node (ref "R5") (pin "1") (pinfunction "1_1") (pintype "passive"))
      (node (ref "U$2") (pin "3") (pinfunction "EN1_3") (pintype "input"))
      (node (ref "U$2") (pin "6") (pinfunction "~{EN2}_6") (pintype "input"))
    )
    (net (code "50") (name "Net-(U$4-BYPASS)") (class "Default")
      (node (ref "C26") (pin "1") (pinfunction "1_1") (pintype "passive"))
      (node (ref "U$4") (pin "4") (pinfunction "BYPASS_4") (pintype "passive"))
    )
    (net (code "51") (name "Net-(U$5-FEED)") (class "Default")
      (node (ref "U$5") (pin "P$2") (pinfunction "FEED_P$2") (pintype "bidirectional"))
      (node (ref "U$6") (pin "11") (pinfunction "RF_IN_11") (pintype "input"))
    )
    (net (code "52") (name "Net-(U$6-EXTINT)") (class "Default")
      (node (ref "FB3") (pin "1") (pinfunction "1_1") (pintype "passive"))
      (node (ref "U$6") (pin "5") (pinfunction "EXTINT_5") (pintype "input"))
    )
    (net (code "53") (name "Net-(U$6-RXD)") (class "Default")
      (node (ref "FB0") (pin "2") (pinfunction "2_2") (pintype "passive"))
      (node (ref "U$6") (pin "3") (pinfunction "RXD_3") (pintype "input"))
    )
    (net (code "54") (name "Net-(U$6-TIMEPULSE)") (class "Default")
      (node (ref "FB2") (pin "1") (pinfunction "1_1") (pintype "passive"))
      (node (ref "U$6") (pin "4") (pinfunction "TIMEPULSE_4") (pintype "output"))
    )
    (net (code "55") (name "Net-(U$6-TXD)") (class "Default")
      (node (ref "FB1") (pin "2") (pinfunction "2_2") (pintype "passive"))
      (node (ref "U$6") (pin "2") (pinfunction "TXD_2") (pintype "output"))
    )
    (net (code "56") (name "Net-(X1-D+)") (class "Default")
      (node (ref "R26") (pin "1") (pinfunction "1_1") (pintype "passive"))
      (node (ref "VAR2") (pin "1") (pinfunction "1_1") (pintype "passive"))
      (node (ref "X1") (pin "3") (pinfunction "D+_3") (pintype "passive"))
    )
    (net (code "57") (name "Net-(X1-SHIELD)") (class "Default")
      (node (ref "L1") (pin "2") (pinfunction "2_2") (pintype "passive"))
      (node (ref "VAR1") (pin "2") (pinfunction "2_2") (pintype "passive"))
      (node (ref "VAR2") (pin "2") (pinfunction "2_2") (pintype "passive"))
      (node (ref "X1") (pin "6") (pinfunction "SHIELD_6") (pintype "passive"))
    )
    (net (code "58") (name "Net-(X1-VBUS)") (class "Default")
      (node (ref "C20") (pin "2") (pinfunction "2_2") (pintype "passive"))
      (node (ref "FUSE1") (pin "2") (pinfunction "2_2") (pintype "bidirectional"))
      (node (ref "X1") (pin "1") (pinfunction "VBUS_1") (pintype "passive"))
    )
    (net (code "59") (name "VBUS") (class "Default")
      (node (ref "C21") (pin "2") (pinfunction "2_2") (pintype "passive"))
      (node (ref "C27") (pin "+") (pinfunction "+_+") (pintype "passive"))
      (node (ref "C28") (pin "+") (pinfunction "+_+") (pintype "passive"))
      (node (ref "FUSE1") (pin "1") (pinfunction "1_1") (pintype "bidirectional"))
      (node (ref "IC3") (pin "20") (pinfunction "VCC_20") (pintype "power_in"))
      (node (ref "R27") (pin "1") (pinfunction "1_1") (pintype "passive"))
      (node (ref "U$4") (pin "1") (pinfunction "IN_1") (pintype "power_in"))
      (node (ref "U$4") (pin "3") (pinfunction "~{SHDN}_3") (pintype "input"))
    )
    (net (code "60") (name "VCC") (class "Default")
      (node (ref "C1") (pin "2") (pinfunction "2_2") (pintype "passive"))
      (node (ref "C10") (pin "1") (pinfunction "1_1") (pintype "passive"))
      (node (ref "C11") (pin "2") (pinfunction "2_2") (pintype "passive"))
      (node (ref "C12") (pin "2") (pinfunction "2_2") (pintype "passive"))
      (node (ref "C18") (pin "1") (pinfunction "1_1") (pintype "passive"))
      (node (ref "C2") (pin "2") (pinfunction "2_2") (pintype "passive"))
      (node (ref "C3") (pin "2") (pinfunction "2_2") (pintype "passive"))
      (node (ref "C4") (pin "2") (pinfunction "2_2") (pintype "passive"))
      (node (ref "C5") (pin "2") (pinfunction "2_2") (pintype "passive"))
      (node (ref "C6") (pin "2") (pinfunction "2_2") (pintype "passive"))
      (node (ref "C7") (pin "1") (pinfunction "1_1") (pintype "passive"))
      (node (ref "C8") (pin "1") (pinfunction "1_1") (pintype "passive"))
      (node (ref "C9") (pin "1") (pinfunction "1_1") (pintype "passive"))
      (node (ref "IC1") (pin "22") (pinfunction "DVCC1_22") (pintype "power_in"))
      (node (ref "IC1") (pin "47") (pinfunction "DVCC2_47") (pintype "power_in"))
      (node (ref "IC1") (pin "60") (pinfunction "ESIDVCC_60") (pintype "power_in"))
      (node (ref "IC1") (pin "64") (pinfunction "AVCC1_64") (pintype "power_in"))
      (node (ref "IC1") (pin "79") (pinfunction "DVCC3_79") (pintype "power_in"))
      (node (ref "R1") (pin "1") (pinfunction "1_1") (pintype "passive"))
      (node (ref "R2") (pin "2") (pinfunction "2_2") (pintype "passive"))
      (node (ref "R3") (pin "2") (pinfunction "2_2") (pintype "passive"))
      (node (ref "S1") (pin "1") (pinfunction "S_1") (pintype "passive"))
      (node (ref "S1") (pin "2") (pinfunction "S1_2") (pintype "passive"))
      (node (ref "S2") (pin "3.1") (pinfunction "3.1_3.1") (pintype "passive"))
      (node (ref "S2") (pin "3.2") (pinfunction "3.2_3.2") (pintype "passive"))
      (node (ref "TP-VCC") (pin "TP") (pinfunction "TP_TP") (pintype "input"))
      (node (ref "U$1") (pin "6") (pinfunction "VCC_6") (pintype "power_in"))
      (node (ref "U$2") (pin "10") (pinfunction "PWRO2_10") (pintype "power_in"))
      (node (ref "U$2") (pin "15") (pinfunction "PWRO1_15") (pintype "power_in"))
      (node (ref "U$2") (pin "16") (pinfunction "PWRO1_16") (pintype "power_in"))
      (node (ref "U$2") (pin "9") (pinfunction "PWRO2_9") (pintype "power_in"))
    )
    (net (code "61") (name "VCC1_IN") (class "Default")
      (node (ref "C25") (pin "1") (pinfunction "1_1") (pintype "passive"))
      (node (ref "G2") (pin "+") (pinfunction "+_+") (pintype "passive"))
      (node (ref "U$2") (pin "7") (pinfunction "PWRI2_7") (pintype "power_in"))
      (node (ref "U$2") (pin "8") (pinfunction "PWRI2_8") (pintype "power_in"))
    )
    (net (code "62") (name "VCC2_IN") (class "Default")
      (node (ref "C22") (pin "+") (pinfunction "+_+") (pintype "passive"))
      (node (ref "IC3") (pin "4") (pinfunction "VCCIO_4") (pintype "power_in"))
      (node (ref "JP1") (pin "1") (pinfunction "1_1") (pintype "passive"))
      (node (ref "LED2") (pin "2") (pinfunction "2_2") (pintype "passive"))
      (node (ref "LED2") (pin "4") (pinfunction "4_4") (pintype "passive"))
      (node (ref "R10") (pin "1") (pinfunction "1_1") (pintype "passive"))
      (node (ref "R9") (pin "1") (pinfunction "1_1") (pintype "passive"))
      (node (ref "U$4") (pin "5") (pinfunction "OUT_5") (pintype "power_in"))
    )
    (net (code "63") (name "unconnected-(IC1-ESICI-Pad62)") (class "Default")
      (node (ref "IC1") (pin "62") (pinfunction "ESICI_62") (pintype "bidirectional"))
    )
    (net (code "64") (name "unconnected-(IC1-ESICOM-Pad63)") (class "Default")
      (node (ref "IC1") (pin "63") (pinfunction "ESICOM_63") (pintype "bidirectional"))
    )
    (net (code "65") (name "unconnected-(IC1-P1.0{slash}TA0.1{slash}DMAE0{slash}RTCCLK{slash}A0{slash}C0{slash}VREF-{slash}VEREF--Pad51)") (class "Default")
      (node (ref "IC1") (pin "51") (pinfunction "P1.0/TA0.1/DMAE0/RTCCLK/A0/C0/VREF-/VEREF-_51") (pintype "bidirectional"))
    )
    (net (code "66") (name "unconnected-(IC1-P1.2{slash}TA1.1{slash}TA0CLK{slash}COUT{slash}A2{slash}C2-Pad49)") (class "Default")
      (node (ref "IC1") (pin "49") (pinfunction "P1.2/TA1.1/TA0CLK/COUT/A2/C2_49") (pintype "bidirectional"))
    )
    (net (code "67") (name "unconnected-(IC1-P1.3{slash}TA1.2{slash}ESITEST4{slash}A3{slash}C3-Pad48)") (class "Default")
      (node (ref "IC1") (pin "48") (pinfunction "P1.3/TA1.2/ESITEST4/A3/C3_48") (pintype "bidirectional"))
    )
    (net (code "68") (name "unconnected-(IC1-P2.0{slash}UCA0SIMO{slash}UCA0TXD{slash}TB0.6{slash}TB0CLK{slash}S14-Pad41)") (class "Default")
      (node (ref "IC1") (pin "41") (pinfunction "P2.0/UCA0SIMO/UCA0TXD/TB0.6/TB0CLK/S14_41") (pintype "bidirectional"))
    )
    (net (code "69") (name "unconnected-(IC1-P2.3{slash}UCA0STE{slash}TB0OUTH{slash}S17-Pad38)") (class "Default")
      (node (ref "IC1") (pin "38") (pinfunction "P2.3/UCA0STE/TB0OUTH/S17_38") (pintype "bidirectional"))
    )
    (net (code "70") (name "unconnected-(IC1-P2.4{slash}TB0.3{slash}COM4{slash}S33-Pad14)") (class "Default")
      (node (ref "IC1") (pin "14") (pinfunction "P2.4/TB0.3/COM4/S33_14") (pintype "bidirectional"))
    )
    (net (code "71") (name "unconnected-(IC1-P2.5{slash}TB0.4{slash}COM5{slash}S32-Pad15)") (class "Default")
      (node (ref "IC1") (pin "15") (pinfunction "P2.5/TB0.4/COM5/S32_15") (pintype "bidirectional"))
    )
    (net (code "72") (name "unconnected-(IC1-P2.6{slash}TB0.5{slash}ESIC1OUT{slash}COM6{slash}S31-Pad16)") (class "Default")
      (node (ref "IC1") (pin "16") (pinfunction "P2.6/TB0.5/ESIC1OUT/COM6/S31_16") (pintype "bidirectional"))
    )
    (net (code "73") (name "unconnected-(IC1-P2.7{slash}TB0.6{slash}ESIC2OUT{slash}COM7{slash}S30-Pad17)") (class "Default")
      (node (ref "IC1") (pin "17") (pinfunction "P2.7/TB0.6/ESIC2OUT/COM7/S30_17") (pintype "bidirectional"))
    )
    (net (code "74") (name "unconnected-(IC1-P3.0{slash}UCB1CLK{slash}S29-Pad18)") (class "Default")
      (node (ref "IC1") (pin "18") (pinfunction "P3.0/UCB1CLK/S29_18") (pintype "bidirectional"))
    )
    (net (code "75") (name "unconnected-(IC1-P3.1{slash}UCB1SIMO{slash}UCB1SDA{slash}S28-Pad19)") (class "Default")
      (node (ref "IC1") (pin "19") (pinfunction "P3.1/UCB1SIMO/UCB1SDA/S28_19") (pintype "bidirectional"))
    )
    (net (code "76") (name "unconnected-(IC1-P3.3{slash}TA1.1{slash}TB0CLK{slash}S22-Pad33)") (class "Default")
      (node (ref "IC1") (pin "33") (pinfunction "P3.3/TA1.1/TB0CLK/S22_33") (pintype "bidirectional"))
    )
    (net (code "77") (name "unconnected-(IC1-P3.6{slash}UCA1CLK{slash}TB0.2{slash}S19-Pad36)") (class "Default")
      (node (ref "IC1") (pin "36") (pinfunction "P3.6/UCA1CLK/TB0.2/S19_36") (pintype "bidirectional"))
    )
    (net (code "78") (name "unconnected-(IC1-P4.0{slash}UCB1SIMO{slash}UCB1SDA{slash}MCLK{slash}S5-Pad76)") (class "Default")
      (node (ref "IC1") (pin "76") (pinfunction "P4.0/UCB1SIMO/UCB1SDA/MCLK/S5_76") (pintype "bidirectional"))
    )
    (net (code "79") (name "unconnected-(IC1-P4.1{slash}UCB1SOMI{slash}UCB1SCL{slash}ACLK{slash}S4-Pad77)") (class "Default")
      (node (ref "IC1") (pin "77") (pinfunction "P4.1/UCB1SOMI/UCB1SCL/ACLK/S4_77") (pintype "bidirectional"))
    )
    (net (code "80") (name "unconnected-(IC1-P4.4{slash}UCB1STE{slash}TA1CLK{slash}S9-Pad72)") (class "Default")
      (node (ref "IC1") (pin "72") (pinfunction "P4.4/UCB1STE/TA1CLK/S9_72") (pintype "bidirectional"))
    )
    (net (code "81") (name "unconnected-(IC1-P4.5{slash}UCB1CLK{slash}TA1.0{slash}S8-Pad73)") (class "Default")
      (node (ref "IC1") (pin "73") (pinfunction "P4.5/UCB1CLK/TA1.0/S8_73") (pintype "bidirectional"))
    )
    (net (code "82") (name "unconnected-(IC1-P4.6{slash}UCB1SIMO{slash}UCB1SDA{slash}TA1.1{slash}S7-Pad74)") (class "Default")
      (node (ref "IC1") (pin "74") (pinfunction "P4.6/UCB1SIMO/UCB1SDA/TA1.1/S7_74") (pintype "bidirectional"))
    )
    (net (code "83") (name "unconnected-(IC1-P4.7{slash}UCB1SOMI{slash}UCB1SCL{slash}TA1.2{slash}S6-Pad75)") (class "Default")
      (node (ref "IC1") (pin "75") (pinfunction "P4.7/UCB1SOMI/UCB1SCL/TA1.2/S6_75") (pintype "bidirectional"))
    )
    (net (code "84") (name "unconnected-(IC1-P6.0{slash}R23-Pad7)") (class "Default")
      (node (ref "IC1") (pin "7") (pinfunction "P6.0/R23_7") (pintype "bidirectional"))
    )
    (net (code "85") (name "unconnected-(IC1-P6.1{slash}R13{slash}LCDREF-Pad8)") (class "Default")
      (node (ref "IC1") (pin "8") (pinfunction "P6.1/R13/LCDREF_8") (pintype "bidirectional"))
    )
    (net (code "86") (name "unconnected-(IC1-P6.2{slash}COUT{slash}R03-Pad9)") (class "Default")
      (node (ref "IC1") (pin "9") (pinfunction "P6.2/COUT/R03_9") (pintype "bidirectional"))
    )
    (net (code "87") (name "unconnected-(IC1-P6.3{slash}COM0-Pad10)") (class "Default")
      (node (ref "IC1") (pin "10") (pinfunction "P6.3/COM0_10") (pintype "bidirectional"))
    )
    (net (code "88") (name "unconnected-(IC1-P6.4{slash}TB0.0{slash}COM1{slash}S36-Pad11)") (class "Default")
      (node (ref "IC1") (pin "11") (pinfunction "P6.4/TB0.0/COM1/S36_11") (pintype "bidirectional"))
    )
    (net (code "89") (name "unconnected-(IC1-P6.5{slash}TB0.1{slash}COM2{slash}S35-Pad12)") (class "Default")
      (node (ref "IC1") (pin "12") (pinfunction "P6.5/TB0.1/COM2/S35_12") (pintype "bidirectional"))
    )
    (net (code "90") (name "unconnected-(IC1-P6.6{slash}TB0.2{slash}COM3{slash}S34-Pad13)") (class "Default")
      (node (ref "IC1") (pin "13") (pinfunction "P6.6/TB0.2/COM3/S34_13") (pintype "bidirectional"))
    )
    (net (code "91") (name "unconnected-(IC1-P6.7{slash}TA0CLK{slash}S26-Pad29)") (class "Default")
      (node (ref "IC1") (pin "29") (pinfunction "P6.7/TA0CLK/S26_29") (pintype "bidirectional"))
    )
    (net (code "92") (name "unconnected-(IC1-P7.0{slash}TA0CLK{slash}S13-Pad42)") (class "Default")
      (node (ref "IC1") (pin "42") (pinfunction "P7.0/TA0CLK/S13_42") (pintype "bidirectional"))
    )
    (net (code "93") (name "unconnected-(IC1-P7.1{slash}TA0.0{slash}S12-Pad43)") (class "Default")
      (node (ref "IC1") (pin "43") (pinfunction "P7.1/TA0.0/S12_43") (pintype "bidirectional"))
    )
    (net (code "94") (name "unconnected-(IC1-P7.2{slash}TA0.1{slash}S11-Pad44)") (class "Default")
      (node (ref "IC1") (pin "44") (pinfunction "P7.2/TA0.1/S11_44") (pintype "bidirectional"))
    )
    (net (code "95") (name "unconnected-(IC1-P7.3{slash}TA0.2{slash}S10-Pad45)") (class "Default")
      (node (ref "IC1") (pin "45") (pinfunction "P7.3/TA0.2/S10_45") (pintype "bidirectional"))
    )
    (net (code "96") (name "unconnected-(IC1-P7.5{slash}TA0.2{slash}S25-Pad30)") (class "Default")
      (node (ref "IC1") (pin "30") (pinfunction "P7.5/TA0.2/S25_30") (pintype "bidirectional"))
    )
    (net (code "97") (name "unconnected-(IC1-P9.1{slash}ESICH1{slash}ESITEST1{slash}A9{slash}C9-Pad53)") (class "Default")
      (node (ref "IC1") (pin "53") (pinfunction "P9.1/ESICH1/ESITEST1/A9/C9_53") (pintype "bidirectional"))
    )
    (net (code "98") (name "unconnected-(IC1-P9.2{slash}ESICH2{slash}ESITEST2{slash}A10{slash}C10-Pad54)") (class "Default")
      (node (ref "IC1") (pin "54") (pinfunction "P9.2/ESICH2/ESITEST2/A10/C10_54") (pintype "bidirectional"))
    )
    (net (code "99") (name "unconnected-(IC1-P9.3{slash}ESICH3{slash}ESITEST3{slash}A11{slash}C11-Pad55)") (class "Default")
      (node (ref "IC1") (pin "55") (pinfunction "P9.3/ESICH3/ESITEST3/A11/C11_55") (pintype "bidirectional"))
    )
    (net (code "100") (name "unconnected-(IC1-P9.4{slash}ESICI0{slash}A12{slash}C12-Pad56)") (class "Default")
      (node (ref "IC1") (pin "56") (pinfunction "P9.4/ESICI0/A12/C12_56") (pintype "bidirectional"))
    )
    (net (code "101") (name "unconnected-(IC1-P9.5{slash}ESICI1{slash}A13{slash}C13-Pad57)") (class "Default")
      (node (ref "IC1") (pin "57") (pinfunction "P9.5/ESICI1/A13/C13_57") (pintype "bidirectional"))
    )
    (net (code "102") (name "unconnected-(IC1-P9.6{slash}ESICI2{slash}A14{slash}C14-Pad58)") (class "Default")
      (node (ref "IC1") (pin "58") (pinfunction "P9.6/ESICI2/A14/C14_58") (pintype "bidirectional"))
    )
    (net (code "103") (name "unconnected-(IC1-P9.7{slash}ESICI3{slash}A15{slash}C15-Pad59)") (class "Default")
      (node (ref "IC1") (pin "59") (pinfunction "P9.7/ESICI3/A15/C15_59") (pintype "bidirectional"))
    )
    (net (code "104") (name "unconnected-(IC1-PJ.0{slash}TDO{slash}TB0OUTH{slash}SMCLK{slash}SRSCG1-Pad25)") (class "Default")
      (node (ref "IC1") (pin "25") (pinfunction "PJ.0/TDO/TB0OUTH/SMCLK/SRSCG1_25") (pintype "bidirectional"))
    )
    (net (code "105") (name "unconnected-(IC1-PJ.1{slash}TDI{slash}TCLK{slash}MCLK{slash}SRSCG0-Pad26)") (class "Default")
      (node (ref "IC1") (pin "26") (pinfunction "PJ.1/TDI/TCLK/MCLK/SRSCG0_26") (pintype "bidirectional"))
    )
    (net (code "106") (name "unconnected-(IC1-PJ.2{slash}TMS{slash}ACLK{slash}SROSCOFF-Pad27)") (class "Default")
      (node (ref "IC1") (pin "27") (pinfunction "PJ.2/TMS/ACLK/SROSCOFF_27") (pintype "bidirectional"))
    )
    (net (code "107") (name "unconnected-(IC1-PJ.3{slash}TCK{slash}COUT{slash}SRCPUOFF-Pad28)") (class "Default")
      (node (ref "IC1") (pin "28") (pinfunction "PJ.3/TCK/COUT/SRCPUOFF_28") (pintype "bidirectional"))
    )
    (net (code "108") (name "unconnected-(IC1-PJ.4{slash}LFXIN-Pad69)") (class "Default")
      (node (ref "IC1") (pin "69") (pinfunction "PJ.4/LFXIN_69") (pintype "bidirectional"))
    )
    (net (code "109") (name "unconnected-(IC1-PJ.5{slash}LFXOUT-Pad70)") (class "Default")
      (node (ref "IC1") (pin "70") (pinfunction "PJ.5/LFXOUT_70") (pintype "bidirectional"))
    )
    (net (code "110") (name "unconnected-(IC1-PJ.6{slash}HFXIN-Pad67)") (class "Default")
      (node (ref "IC1") (pin "67") (pinfunction "PJ.6/HFXIN_67") (pintype "bidirectional"))
    )
    (net (code "111") (name "unconnected-(IC1-PJ.7{slash}HFXOUT-Pad66)") (class "Default")
      (node (ref "IC1") (pin "66") (pinfunction "PJ.7/HFXOUT_66") (pintype "bidirectional"))
    )
    (net (code "112") (name "unconnected-(IC3-CBUS2-Pad13)") (class "Default")
      (node (ref "IC3") (pin "13") (pinfunction "CBUS2_13") (pintype "bidirectional"))
    )
    (net (code "113") (name "unconnected-(IC3-CBUS3-Pad14)") (class "Default")
      (node (ref "IC3") (pin "14") (pinfunction "CBUS3_14") (pintype "bidirectional"))
    )
    (net (code "114") (name "unconnected-(IC3-CBUS4-Pad12)") (class "Default")
      (node (ref "IC3") (pin "12") (pinfunction "CBUS4_12") (pintype "bidirectional"))
    )
    (net (code "115") (name "unconnected-(IC3-OSCI-Pad27)") (class "Default")
      (node (ref "IC3") (pin "27") (pinfunction "OSCI_27") (pintype "input"))
    )
    (net (code "116") (name "unconnected-(IC3-OSCO-Pad28)") (class "Default")
      (node (ref "IC3") (pin "28") (pinfunction "OSCO_28") (pintype "output"))
    )
    (net (code "117") (name "unconnected-(IC3-~{CTS}-Pad11)") (class "Default")
      (node (ref "IC3") (pin "11") (pinfunction "~{CTS}_11") (pintype "input"))
    )
    (net (code "118") (name "unconnected-(IC3-~{DCD}-Pad10)") (class "Default")
      (node (ref "IC3") (pin "10") (pinfunction "~{DCD}_10") (pintype "input"))
    )
    (net (code "119") (name "unconnected-(IC3-~{DSR}-Pad9)") (class "Default")
      (node (ref "IC3") (pin "9") (pinfunction "~{DSR}_9") (pintype "input"))
    )
    (net (code "120") (name "unconnected-(IC3-~{DTR}-Pad2)") (class "Default")
      (node (ref "IC3") (pin "2") (pinfunction "~{DTR}_2") (pintype "output"))
    )
    (net (code "121") (name "unconnected-(IC3-~{RESET}-Pad19)") (class "Default")
      (node (ref "IC3") (pin "19") (pinfunction "~{RESET}_19") (pintype "input"))
    )
    (net (code "122") (name "unconnected-(IC3-~{RI}-Pad6)") (class "Default")
      (node (ref "IC3") (pin "6") (pinfunction "~{RI}_6") (pintype "input"))
    )
    (net (code "123") (name "unconnected-(IC3-~{RTS}-Pad3)") (class "Default")
      (node (ref "IC3") (pin "3") (pinfunction "~{RTS}_3") (pintype "output"))
    )
    (net (code "124") (name "unconnected-(U$2-STAT1-Pad14)") (class "Default")
      (node (ref "U$2") (pin "14") (pinfunction "STAT1_14") (pintype "bidirectional"))
    )
    (net (code "125") (name "unconnected-(U$2-STAT2-Pad11)") (class "Default")
      (node (ref "U$2") (pin "11") (pinfunction "STAT2_11") (pintype "bidirectional"))
    )
    (net (code "126") (name "unconnected-(U$2-WARN1-Pad13)") (class "Default")
      (node (ref "U$2") (pin "13") (pinfunction "WARN1_13") (pintype "bidirectional"))
    )
    (net (code "127") (name "unconnected-(U$2-WARN2-Pad12)") (class "Default")
      (node (ref "U$2") (pin "12") (pinfunction "WARN2_12") (pintype "bidirectional"))
    )
    (net (code "128") (name "unconnected-(U$6-ANT_ON-Pad13)") (class "Default")
      (node (ref "U$6") (pin "13") (pinfunction "ANT_ON_13") (pintype "output"))
    )
    (net (code "129") (name "unconnected-(U$6-SCL-Pad17)") (class "Default")
      (node (ref "U$6") (pin "17") (pinfunction "SCL_17") (pintype "input"))
    )
    (net (code "130") (name "unconnected-(U$6-SDA-Pad16)") (class "Default")
      (node (ref "U$6") (pin "16") (pinfunction "SDA_16") (pintype "bidirectional"))
    )
    (net (code "131") (name "unconnected-(U$6-VCC_RF-Pad14)") (class "Default")
      (node (ref "U$6") (pin "14") (pinfunction "VCC_RF_14") (pintype "output"))
    )
    (net (code "132") (name "unconnected-(U$6-~{RESET}-Pad9)") (class "Default")
      (node (ref "U$6") (pin "9") (pinfunction "~{RESET}_9") (pintype "bidirectional"))
    )
    (net (code "133") (name "unconnected-(X1-ID-Pad4)") (class "Default")
      (node (ref "X1") (pin "4") (pinfunction "ID_4") (pintype "passive"))
    )
  )
)
